# motor_pcb.net
KiCad netlist of a schematic drawn in EAGLE
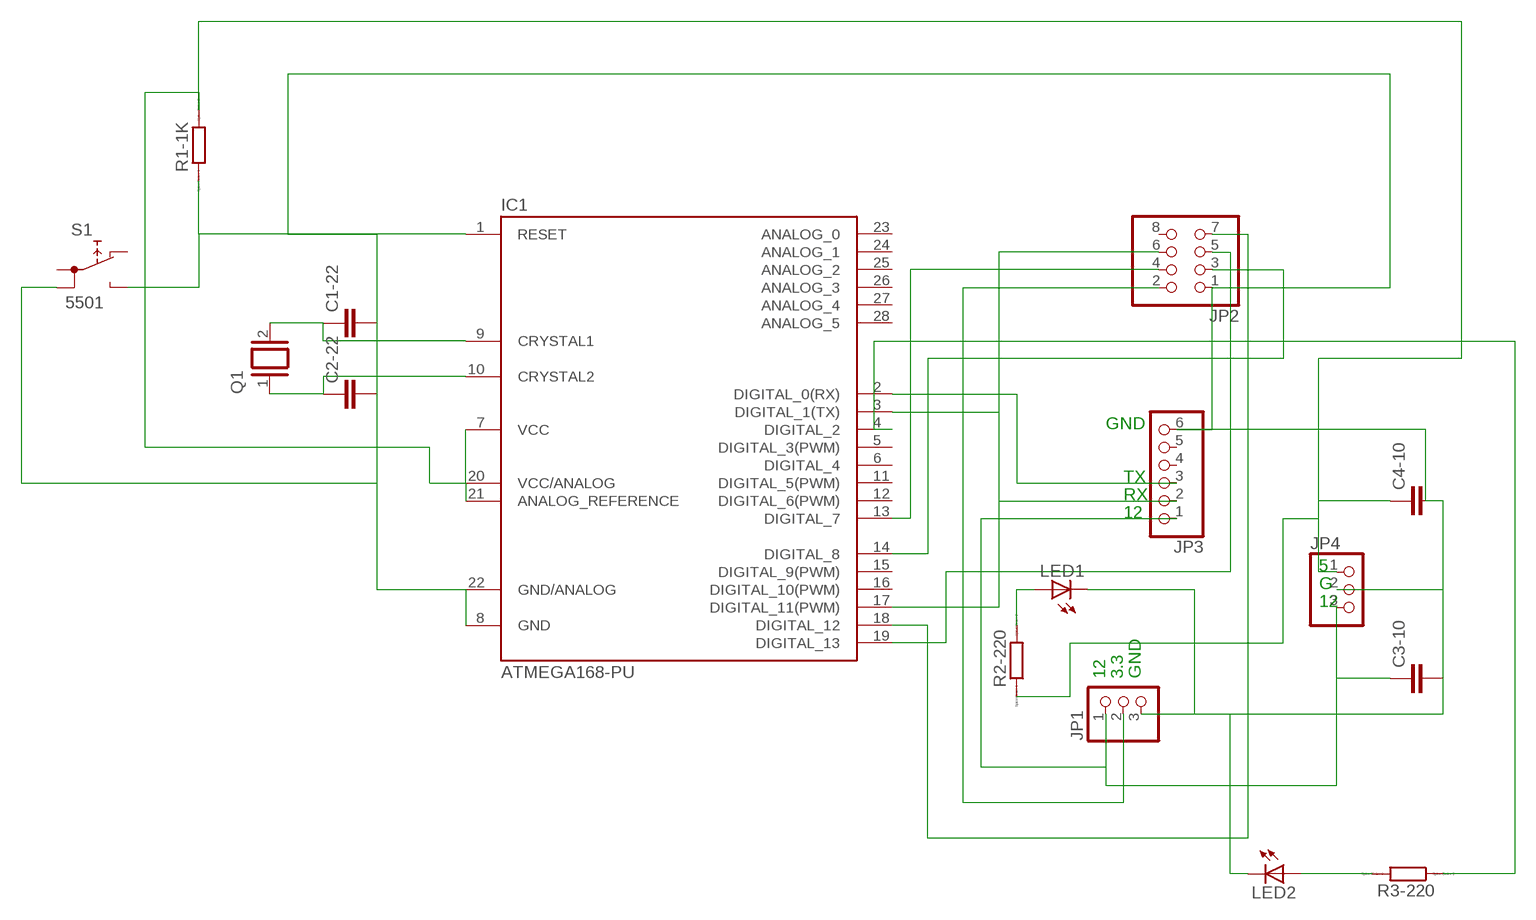
[diagram p0: schematic, sheet 1]

(export (version "E")
  (design (tool "Eeschema 10.0.6"))
  (components
    (comp (ref "C1-22")
      (value "C2.5/2")
      (footprint "eagle-import:C2.5-2")
      (libsource (lib "eagle-import") (part "C2.5/2"))
    )
    (comp (ref "C2-22")
      (value "C2.5/2")
      (footprint "eagle-import:C2.5-2")
      (libsource (lib "eagle-import") (part "C2.5/2"))
    )
    (comp (ref "C3-10")
      (value "C2.5/2")
      (footprint "eagle-import:C2.5-2")
      (libsource (lib "eagle-import") (part "C2.5/2"))
    )
    (comp (ref "C4-10")
      (value "C2.5/2")
      (footprint "eagle-import:C2.5-2")
      (libsource (lib "eagle-import") (part "C2.5/2"))
    )
    (comp (ref "IC1")
      (value "ATMEGA168-PU")
      (footprint "eagle-import:DIL28-3")
      (libsource (lib "eagle-import") (part "ATMEGA168-PU"))
    )
    (comp (ref "JP1")
      (value "PINHD-1X3")
      (footprint "eagle-import:1X03")
      (libsource (lib "eagle-import") (part "PINHD-1X3"))
    )
    (comp (ref "JP2")
      (value "PINHD-2X4")
      (footprint "eagle-import:2X04")
      (libsource (lib "eagle-import") (part "PINHD-2X4"))
    )
    (comp (ref "JP3")
      (value "PINHD-1X6")
      (footprint "eagle-import:1X06")
      (libsource (lib "eagle-import") (part "PINHD-1X6"))
    )
    (comp (ref "JP4")
      (value "PINHD-1X3")
      (footprint "eagle-import:1X03")
      (libsource (lib "eagle-import") (part "PINHD-1X3"))
    )
    (comp (ref "LED1")
      (value "LED3MM")
      (footprint "eagle-import:LED3MM")
      (libsource (lib "eagle-import") (part "LED3MM"))
    )
    (comp (ref "LED2")
      (value "LED3MM")
      (footprint "eagle-import:LED3MM")
      (libsource (lib "eagle-import") (part "LED3MM"))
    )
    (comp (ref "Q1")
      (value "XTAL/S")
      (footprint "eagle-import:QS")
      (libsource (lib "eagle-import") (part "XTAL/S"))
    )
    (comp (ref "R1-1K")
      (value "R0204/7")
      (footprint "eagle-import:0204_7")
      (libsource (lib "eagle-import") (part "R0204/7"))
    )
    (comp (ref "R2-220")
      (value "R0204/7")
      (footprint "eagle-import:0204_7")
      (libsource (lib "eagle-import") (part "R0204/7"))
    )
    (comp (ref "R3-220")
      (value "R0204/7")
      (footprint "eagle-import:0204_7")
      (libsource (lib "eagle-import") (part "R0204/7"))
    )
    (comp (ref "S1")
      (value "5501")
      (footprint "eagle-import:5501")
      (libsource (lib "eagle-import") (part "55?01"))
    )
  )
  (nets
    (net (code "1") (name "Net-(C3-10-Pad1)") (class "Default")
      (node (ref "C3-10") (pin "1") (pinfunction "1_1") (pintype "passive"))
      (node (ref "JP1") (pin "1") (pinfunction "1_1") (pintype "passive"))
      (node (ref "JP4") (pin "3") (pinfunction "3_3") (pintype "passive"))
    )
    (net (code "2") (name "Net-(IC1-ANALOG_REFERENCE)") (class "Default")
      (node (ref "C4-10") (pin "1") (pinfunction "1_1") (pintype "passive"))
      (node (ref "IC1") (pin "20") (pinfunction "VCC/ANALOG_20") (pintype "passive"))
      (node (ref "IC1") (pin "21") (pinfunction "ANALOG_REFERENCE_21") (pintype "passive"))
      (node (ref "IC1") (pin "7") (pinfunction "VCC_7") (pintype "power_in"))
      (node (ref "JP4") (pin "1") (pinfunction "1_1") (pintype "passive"))
      (node (ref "R1-1K") (pin "2") (pinfunction "2_2") (pintype "passive"))
    )
    (net (code "3") (name "Net-(IC1-CRYSTAL1)") (class "Default")
      (node (ref "C1-22") (pin "1") (pinfunction "1_1") (pintype "passive"))
      (node (ref "IC1") (pin "9") (pinfunction "CRYSTAL1_9") (pintype "bidirectional"))
      (node (ref "Q1") (pin "2") (pinfunction "2_2") (pintype "passive"))
    )
    (net (code "4") (name "Net-(IC1-CRYSTAL2)") (class "Default")
      (node (ref "C2-22") (pin "1") (pinfunction "1_1") (pintype "passive"))
      (node (ref "IC1") (pin "10") (pinfunction "CRYSTAL2_10") (pintype "bidirectional"))
      (node (ref "Q1") (pin "1") (pinfunction "1_1") (pintype "passive"))
    )
    (net (code "5") (name "Net-(IC1-DIGITAL_0(RX))") (class "Default")
      (node (ref "IC1") (pin "2") (pinfunction "DIGITAL_0(RX)_2") (pintype "bidirectional"))
      (node (ref "JP3") (pin "3") (pinfunction "3_3") (pintype "passive"))
    )
    (net (code "6") (name "Net-(IC1-DIGITAL_1(TX))") (class "Default")
      (node (ref "IC1") (pin "3") (pinfunction "DIGITAL_1(TX)_3") (pintype "bidirectional"))
      (node (ref "JP3") (pin "2") (pinfunction "2_2") (pintype "passive"))
    )
    (net (code "7") (name "Net-(IC1-DIGITAL_2)") (class "Default")
      (node (ref "IC1") (pin "4") (pinfunction "DIGITAL_2_4") (pintype "bidirectional"))
      (node (ref "R3-220") (pin "1") (pinfunction "1_1") (pintype "passive"))
    )
    (net (code "8") (name "Net-(IC1-DIGITAL_7)") (class "Default")
      (node (ref "IC1") (pin "13") (pinfunction "DIGITAL_7_13") (pintype "bidirectional"))
      (node (ref "JP2") (pin "4") (pinfunction "4_4") (pintype "passive"))
    )
    (net (code "9") (name "Net-(IC1-DIGITAL_8)") (class "Default")
      (node (ref "IC1") (pin "14") (pinfunction "DIGITAL_8_14") (pintype "bidirectional"))
      (node (ref "JP2") (pin "3") (pinfunction "3_3") (pintype "passive"))
    )
    (net (code "10") (name "Net-(IC1-DIGITAL_11(PWM))") (class "Default")
      (node (ref "IC1") (pin "17") (pinfunction "DIGITAL_11(PWM)_17") (pintype "bidirectional"))
      (node (ref "JP2") (pin "6") (pinfunction "6_6") (pintype "passive"))
    )
    (net (code "11") (name "Net-(IC1-DIGITAL_12)") (class "Default")
      (node (ref "IC1") (pin "18") (pinfunction "DIGITAL_12_18") (pintype "bidirectional"))
      (node (ref "JP2") (pin "7") (pinfunction "7_7") (pintype "passive"))
    )
    (net (code "12") (name "Net-(IC1-DIGITAL_13)") (class "Default")
      (node (ref "IC1") (pin "19") (pinfunction "DIGITAL_13_19") (pintype "bidirectional"))
      (node (ref "JP2") (pin "5") (pinfunction "5_5") (pintype "passive"))
    )
    (net (code "13") (name "Net-(IC1-GND)") (class "Default")
      (node (ref "C1-22") (pin "2") (pinfunction "2_2") (pintype "passive"))
      (node (ref "C2-22") (pin "2") (pinfunction "2_2") (pintype "passive"))
      (node (ref "C3-10") (pin "2") (pinfunction "2_2") (pintype "passive"))
      (node (ref "C4-10") (pin "2") (pinfunction "2_2") (pintype "passive"))
      (node (ref "IC1") (pin "22") (pinfunction "GND/ANALOG_22") (pintype "power_in"))
      (node (ref "IC1") (pin "8") (pinfunction "GND_8") (pintype "power_in"))
      (node (ref "JP1") (pin "3") (pinfunction "3_3") (pintype "passive"))
      (node (ref "JP2") (pin "1") (pinfunction "1_1") (pintype "passive"))
      (node (ref "JP3") (pin "6") (pinfunction "6_6") (pintype "passive"))
      (node (ref "JP4") (pin "2") (pinfunction "2_2") (pintype "passive"))
      (node (ref "LED2") (pin "K") (pinfunction "C_K") (pintype "passive"))
    )
    (net (code "14") (name "Net-(IC1-RESET)") (class "Default")
      (node (ref "IC1") (pin "1") (pinfunction "RESET_1") (pintype "bidirectional"))
      (node (ref "R1-1K") (pin "1") (pinfunction "1_1") (pintype "passive"))
      (node (ref "S1") (pin "NO") (pinfunction "NO_NO") (pintype "passive"))
    )
    (net (code "15") (name "Net-(JP1-Pad2)") (class "Default")
      (node (ref "JP1") (pin "2") (pinfunction "2_2") (pintype "passive"))
      (node (ref "JP2") (pin "2") (pinfunction "2_2") (pintype "passive"))
    )
    (net (code "16") (name "Net-(LED1-PadA)") (class "Default")
      (node (ref "LED1") (pin "A") (pinfunction "A_A") (pintype "passive"))
      (node (ref "R2-220") (pin "2") (pinfunction "2_2") (pintype "passive"))
    )
    (net (code "17") (name "Net-(LED2-PadA)") (class "Default")
      (node (ref "LED2") (pin "A") (pinfunction "A_A") (pintype "passive"))
      (node (ref "R3-220") (pin "2") (pinfunction "2_2") (pintype "passive"))
    )
    (net (code "18") (name "unconnected-(IC1-ANALOG_0-Pad23)") (class "Default")
      (node (ref "IC1") (pin "23") (pinfunction "ANALOG_0_23") (pintype "bidirectional"))
    )
    (net (code "19") (name "unconnected-(IC1-ANALOG_1-Pad24)") (class "Default")
      (node (ref "IC1") (pin "24") (pinfunction "ANALOG_1_24") (pintype "bidirectional"))
    )
    (net (code "20") (name "unconnected-(IC1-ANALOG_2-Pad25)") (class "Default")
      (node (ref "IC1") (pin "25") (pinfunction "ANALOG_2_25") (pintype "bidirectional"))
    )
    (net (code "21") (name "unconnected-(IC1-ANALOG_3-Pad26)") (class "Default")
      (node (ref "IC1") (pin "26") (pinfunction "ANALOG_3_26") (pintype "bidirectional"))
    )
    (net (code "22") (name "unconnected-(IC1-ANALOG_4-Pad27)") (class "Default")
      (node (ref "IC1") (pin "27") (pinfunction "ANALOG_4_27") (pintype "bidirectional"))
    )
    (net (code "23") (name "unconnected-(IC1-ANALOG_5-Pad28)") (class "Default")
      (node (ref "IC1") (pin "28") (pinfunction "ANALOG_5_28") (pintype "bidirectional"))
    )
    (net (code "24") (name "unconnected-(IC1-DIGITAL_3(PWM)-Pad5)") (class "Default")
      (node (ref "IC1") (pin "5") (pinfunction "DIGITAL_3(PWM)_5") (pintype "bidirectional"))
    )
    (net (code "25") (name "unconnected-(IC1-DIGITAL_4-Pad6)") (class "Default")
      (node (ref "IC1") (pin "6") (pinfunction "DIGITAL_4_6") (pintype "bidirectional"))
    )
    (net (code "26") (name "unconnected-(IC1-DIGITAL_5(PWM)-Pad11)") (class "Default")
      (node (ref "IC1") (pin "11") (pinfunction "DIGITAL_5(PWM)_11") (pintype "bidirectional"))
    )
    (net (code "27") (name "unconnected-(IC1-DIGITAL_6(PWM)-Pad12)") (class "Default")
      (node (ref "IC1") (pin "12") (pinfunction "DIGITAL_6(PWM)_12") (pintype "bidirectional"))
    )
    (net (code "28") (name "unconnected-(IC1-DIGITAL_9(PWM)-Pad15)") (class "Default")
      (node (ref "IC1") (pin "15") (pinfunction "DIGITAL_9(PWM)_15") (pintype "bidirectional"))
    )
    (net (code "29") (name "unconnected-(IC1-DIGITAL_10(PWM)-Pad16)") (class "Default")
      (node (ref "IC1") (pin "16") (pinfunction "DIGITAL_10(PWM)_16") (pintype "bidirectional"))
    )
    (net (code "30") (name "unconnected-(JP2-Pad8)") (class "Default")
      (node (ref "JP2") (pin "8") (pinfunction "8_8") (pintype "passive"))
    )
    (net (code "31") (name "unconnected-(JP3-Pad1)") (class "Default")
      (node (ref "JP3") (pin "1") (pinfunction "1_1") (pintype "passive"))
    )
    (net (code "32") (name "unconnected-(JP3-Pad4)") (class "Default")
      (node (ref "JP3") (pin "4") (pinfunction "4_4") (pintype "passive"))
    )
    (net (code "33") (name "unconnected-(JP3-Pad5)") (class "Default")
      (node (ref "JP3") (pin "5") (pinfunction "5_5") (pintype "passive"))
    )
    (net (code "34") (name "unconnected-(LED1-C-PadK)") (class "Default")
      (node (ref "LED1") (pin "K") (pinfunction "C_K") (pintype "passive"))
    )
    (net (code "35") (name "unconnected-(R2-220-Pad1)") (class "Default")
      (node (ref "R2-220") (pin "1") (pinfunction "1_1") (pintype "passive"))
    )
    (net (code "36") (name "unconnected-(S1-Pad1A)") (class "Default")
      (node (ref "S1") (pin "1A") (pinfunction "1A_1A") (pintype "passive"))
    )
    (net (code "37") (name "unconnected-(S1-Pad1B)") (class "Default")
      (node (ref "S1") (pin "1B") (pinfunction "1B_1B") (pintype "passive"))
    )
    (net (code "38") (name "unconnected-(S1-PadNC)") (class "Default")
      (node (ref "S1") (pin "NC") (pinfunction "NC_NC") (pintype "passive"))
    )
  )
)
